# ESP32Schematic_1.net
KiCad netlist of a schematic drawn in Altium Designer
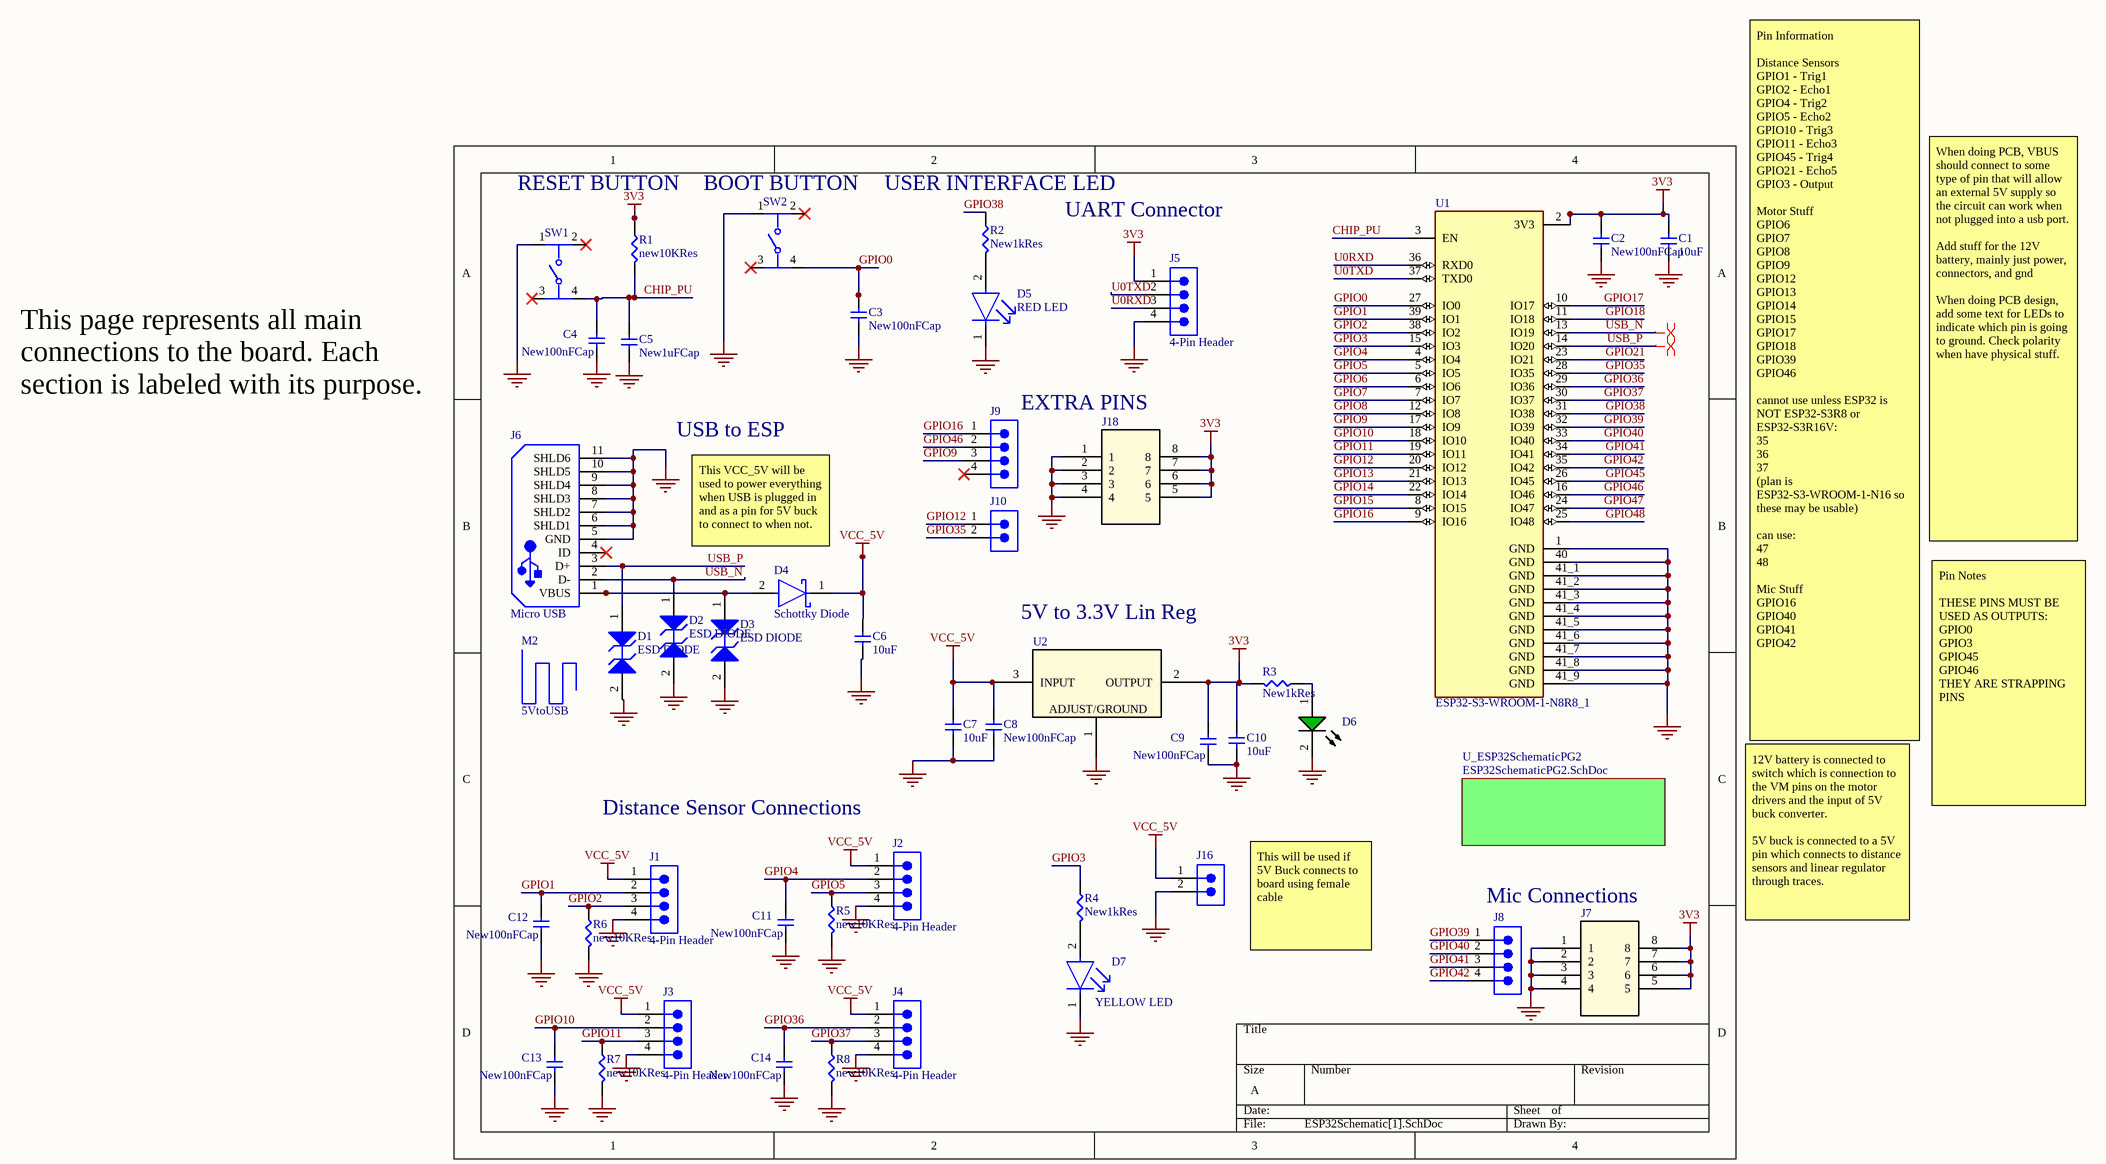
[diagram p0: ESP32Schematic[1].SchDoc]

(export (version "E")
  (design (tool "Eeschema 10.0.6"))
  (components
    (comp (ref "C1")
      (value "10uF")
      (footprint "FP-C0805C106K3PACTU-IPC_C")
      (description "0805 C 10UF Ceramic Multilayer Capacitor, 25 VDC, +85DEGC, X5R Dielec, +/-10%")
      (fields
        (field (name "MANUFACTURER") "KEMET")
        (field (name "MANUFACTURER PART NUMBER") "C0805C106K3PACTU")
      )
      (libsource (lib "Schlib") (part "C0805C106K3PACTU"))
    )
    (comp (ref "C2")
      (value "New100nFCap")
      (footprint "FP-CC0805-0_85-MFG")
      (description "25V 100nF X7R ±10% 0805 Multilayer Ceramic Capacitors MLCC - SMD/SMT ROHS")
      (fields
        (field (name "MANUFACTURER") "KEMET")
        (field (name "MANUFACTURER PART NUMBER") "C0805C104K3RACTU")
      )
      (libsource (lib "Schlib") (part "C0805C104K3RACTU"))
    )
    (comp (ref "C3")
      (value "New100nFCap")
      (footprint "FP-CC0805-0_85-MFG")
      (description "25V 100nF X7R ±10% 0805 Multilayer Ceramic Capacitors MLCC - SMD/SMT ROHS")
      (fields
        (field (name "MANUFACTURER") "KEMET")
        (field (name "MANUFACTURER PART NUMBER") "C0805C104K3RACTU")
      )
      (libsource (lib "Schlib") (part "C0805C104K3RACTU"))
    )
    (comp (ref "C4")
      (value "New100nFCap")
      (footprint "FP-CC0805-0_85-MFG")
      (description "25V 100nF X7R ±10% 0805 Multilayer Ceramic Capacitors MLCC - SMD/SMT ROHS")
      (fields
        (field (name "MANUFACTURER") "KEMET")
        (field (name "MANUFACTURER PART NUMBER") "C0805C104K3RACTU")
      )
      (libsource (lib "Schlib") (part "C0805C104K3RACTU"))
    )
    (comp (ref "C5")
      (value "New1uFCap")
      (footprint "CAPC2013X140X50ML20T25")
      (description "Multilayer Ceramic Capacitors MLCC – SMD/SMT; KEMET; C0805C105K3RACTU; 1 µF; 0805; 25 V; 25 V")
      (fields
        (field (name "MANUFACTURER") "KEMET")
        (field (name "MANUFACTURER PART NUMBER") "C0805C105K3RACTU")
      )
      (libsource (lib "Schlib") (part "C0805C105K3RACTU"))
    )
    (comp (ref "C6")
      (value "10uF")
      (footprint "FP-C0805C106K3PACTU-IPC_C")
      (description "0805 C 10UF Ceramic Multilayer Capacitor, 25 VDC, +85DEGC, X5R Dielec, +/-10%")
      (fields
        (field (name "MANUFACTURER") "KEMET")
        (field (name "MANUFACTURER PART NUMBER") "C0805C106K3PACTU")
      )
      (libsource (lib "Schlib") (part "C0805C106K3PACTU"))
    )
    (comp (ref "C7")
      (value "10uF")
      (footprint "FP-C0805C106K3PACTU-IPC_C")
      (description "0805 C 10UF Ceramic Multilayer Capacitor, 25 VDC, +85DEGC, X5R Dielec, +/-10%")
      (fields
        (field (name "MANUFACTURER") "KEMET")
        (field (name "MANUFACTURER PART NUMBER") "C0805C106K3PACTU")
      )
      (libsource (lib "Schlib") (part "C0805C106K3PACTU"))
    )
    (comp (ref "C8")
      (value "New100nFCap")
      (footprint "FP-CC0805-0_85-MFG")
      (description "25V 100nF X7R ±10% 0805 Multilayer Ceramic Capacitors MLCC - SMD/SMT ROHS")
      (fields
        (field (name "MANUFACTURER") "KEMET")
        (field (name "MANUFACTURER PART NUMBER") "C0805C104K3RACTU")
      )
      (libsource (lib "Schlib") (part "C0805C104K3RACTU"))
    )
    (comp (ref "C9")
      (value "New100nFCap")
      (footprint "FP-CC0805-0_85-MFG")
      (description "25V 100nF X7R ±10% 0805 Multilayer Ceramic Capacitors MLCC - SMD/SMT ROHS")
      (fields
        (field (name "MANUFACTURER") "KEMET")
        (field (name "MANUFACTURER PART NUMBER") "C0805C104K3RACTU")
      )
      (libsource (lib "Schlib") (part "C0805C104K3RACTU"))
    )
    (comp (ref "C10")
      (value "10uF")
      (footprint "FP-C0805C106K3PACTU-IPC_C")
      (description "0805 C 10UF Ceramic Multilayer Capacitor, 25 VDC, +85DEGC, X5R Dielec, +/-10%")
      (fields
        (field (name "MANUFACTURER") "KEMET")
        (field (name "MANUFACTURER PART NUMBER") "C0805C106K3PACTU")
      )
      (libsource (lib "Schlib") (part "C0805C106K3PACTU"))
    )
    (comp (ref "C11")
      (value "New100nFCap")
      (footprint "FP-CC0805-0_85-MFG")
      (description "25V 100nF X7R ±10% 0805 Multilayer Ceramic Capacitors MLCC - SMD/SMT ROHS")
      (fields
        (field (name "MANUFACTURER") "KEMET")
        (field (name "MANUFACTURER PART NUMBER") "C0805C104K3RACTU")
      )
      (libsource (lib "Schlib") (part "C0805C104K3RACTU"))
    )
    (comp (ref "C12")
      (value "New100nFCap")
      (footprint "FP-CC0805-0_85-MFG")
      (description "25V 100nF X7R ±10% 0805 Multilayer Ceramic Capacitors MLCC - SMD/SMT ROHS")
      (fields
        (field (name "MANUFACTURER") "KEMET")
        (field (name "MANUFACTURER PART NUMBER") "C0805C104K3RACTU")
      )
      (libsource (lib "Schlib") (part "C0805C104K3RACTU"))
    )
    (comp (ref "C13")
      (value "New100nFCap")
      (footprint "FP-CC0805-0_85-MFG")
      (description "25V 100nF X7R ±10% 0805 Multilayer Ceramic Capacitors MLCC - SMD/SMT ROHS")
      (fields
        (field (name "MANUFACTURER") "KEMET")
        (field (name "MANUFACTURER PART NUMBER") "C0805C104K3RACTU")
      )
      (libsource (lib "Schlib") (part "C0805C104K3RACTU"))
    )
    (comp (ref "C14")
      (value "New100nFCap")
      (footprint "FP-CC0805-0_85-MFG")
      (description "25V 100nF X7R ±10% 0805 Multilayer Ceramic Capacitors MLCC - SMD/SMT ROHS")
      (fields
        (field (name "MANUFACTURER") "KEMET")
        (field (name "MANUFACTURER PART NUMBER") "C0805C104K3RACTU")
      )
      (libsource (lib "Schlib") (part "C0805C104K3RACTU"))
    )
    (comp (ref "D1")
      (value "ESD DIODE")
      (footprint "ONSC-SOD-923-2-514AB-01_V")
      (description "5.8V Bidirectional 5V SOD-923 ESD and Surge Protection (TVS/ESD) ROHS")
      (fields (field (name "MANUFACTURER") "onsemi") (field (name "MANUFACTURER PART NUMBER") "ESD9B5.0ST5G"))
      (libsource (lib "Schlib") (part "ESD9B5.0ST5G"))
    )
    (comp (ref "D2")
      (value "ESD DIODE")
      (footprint "ONSC-SOD-923-2-514AB-01_V")
      (description "5.8V Bidirectional 5V SOD-923 ESD and Surge Protection (TVS/ESD) ROHS")
      (fields (field (name "MANUFACTURER") "onsemi") (field (name "MANUFACTURER PART NUMBER") "ESD9B5.0ST5G"))
      (libsource (lib "Schlib") (part "ESD9B5.0ST5G"))
    )
    (comp (ref "D3")
      (value "ESD DIODE")
      (footprint "ONSC-SOD-923-2-514AB-01_V")
      (description "5.8V Bidirectional 5V SOD-923 ESD and Surge Protection (TVS/ESD) ROHS")
      (fields (field (name "MANUFACTURER") "onsemi") (field (name "MANUFACTURER PART NUMBER") "ESD9B5.0ST5G"))
      (libsource (lib "Schlib") (part "ESD9B5.0ST5G"))
    )
    (comp (ref "D4")
      (value "Schottky Diode")
      (footprint "FP-SOD123-IPC_B")
      (description "1N5819HW Series 40 V 1 A Surface Mount Schottky Barrier Rectifier - SOD-123")
      (fields
        (field (name "MANUFACTURER") "Diodes Inc.")
        (field (name "MANUFACTURER PART NUMBER") "1N5819HW-7-F")
      )
      (libsource (lib "Schlib") (part "1N5819HW-7-F"))
    )
    (comp (ref "D5")
      (value "RED LED")
      (footprint "FP-HSMS-C150-MFG")
      (description "LED Uni-Color Hi-Eff. Red 630nm 2-Pin Chip LED T/R / LED RED DIFFUSED 1206 SMD")
      (fields (field (name "MANUFACTURER") "Avago") (field (name "MANUFACTURER PART NUMBER") "HSMS-C150"))
      (libsource (lib "Schlib") (part "HSMS-C150"))
    )
    (comp (ref "D6")
      (value "GREEN LED")
      (footprint "AVAG-HSMX-C110_V")
      (description "Surface Mount ChipLED Single Color LED, Green, Clear Untinted Nondiffused")
      (fields (field (name "MANUFACTURER") "Avago") (field (name "MANUFACTURER PART NUMBER") "HSMG-C110"))
      (libsource (lib "Schlib") (part "HSMG-C110"))
    )
    (comp (ref "D7")
      (value "YELLOW LED")
      (footprint "LED_HSMY-C170")
      (description "LED YELLOW DIFFUSED CHIP SMD Yellow 586nm LED Indication - Discrete 2.1V 0805 (2012 Metric)")
      (fields (field (name "MANUFACTURER") "Avago") (field (name "MANUFACTURER PART NUMBER") "HSMY-C170"))
      (libsource (lib "Schlib") (part "HSMY-C170"))
    )
    (comp (ref "J1")
      (value "4-Pin Header")
      (footprint "61300411121")
      (description "Conn Unshrouded Header HDR 4 POS 2.54mm Solder ST Thru-Hole Bag")
      (fields
        (field (name "MANUFACTURER") "Wurth Elektronik")
        (field (name "MANUFACTURER PART NUMBER") "61300411121")
      )
      (libsource (lib "Schlib") (part "61300411121"))
    )
    (comp (ref "J2")
      (value "4-Pin Header")
      (footprint "61300411121")
      (description "Conn Unshrouded Header HDR 4 POS 2.54mm Solder ST Thru-Hole Bag")
      (fields
        (field (name "MANUFACTURER") "Wurth Elektronik")
        (field (name "MANUFACTURER PART NUMBER") "61300411121")
      )
      (libsource (lib "Schlib") (part "61300411121"))
    )
    (comp (ref "J3")
      (value "4-Pin Header")
      (footprint "61300411121")
      (description "Conn Unshrouded Header HDR 4 POS 2.54mm Solder ST Thru-Hole Bag")
      (fields
        (field (name "MANUFACTURER") "Wurth Elektronik")
        (field (name "MANUFACTURER PART NUMBER") "61300411121")
      )
      (libsource (lib "Schlib") (part "61300411121"))
    )
    (comp (ref "J4")
      (value "4-Pin Header")
      (footprint "61300411121")
      (description "Conn Unshrouded Header HDR 4 POS 2.54mm Solder ST Thru-Hole Bag")
      (fields
        (field (name "MANUFACTURER") "Wurth Elektronik")
        (field (name "MANUFACTURER PART NUMBER") "61300411121")
      )
      (libsource (lib "Schlib") (part "61300411121"))
    )
    (comp (ref "J5")
      (value "4-Pin Header")
      (footprint "61300411121")
      (description "Conn Unshrouded Header HDR 4 POS 2.54mm Solder ST Thru-Hole Bag")
      (fields
        (field (name "MANUFACTURER") "Wurth Elektronik")
        (field (name "MANUFACTURER PART NUMBER") "61300411121")
      )
      (libsource (lib "Schlib") (part "61300411121"))
    )
    (comp (ref "J6")
      (value "Micro USB")
      (footprint "FCI-10103594-0001LF_V")
      (description "Usb Connector, 5 Contact(S), Female, Right Angle, Surface Mount Terminal, Locking, Receptacle")
      (fields
        (field (name "MANUFACTURER") "Amphenol Communications Solutions")
        (field (name "MANUFACTURER PART NUMBER") "10103594-0001LF")
      )
      (libsource (lib "Schlib") (part "10103594-0001LF"))
    )
    (comp (ref "J7")
      (value "8pin")
      (footprint "TSW-104-07-G-D_SAI")
      (description "Pin Header, Board-to-Board, 2.54 mm, 2 Rows, 8 Contacts, Through Hole, TSW Series")
      (fields
        (field (name "MANUFACTURER") "Samtec")
        (field (name "MANUFACTURER PART NUMBER") "TSW-104-07-F-D")
      )
      (libsource (lib "Schlib") (part "TSW-104-07-F-D"))
    )
    (comp (ref "J8")
      (value "4-Pin Header")
      (footprint "61300411121")
      (description "Conn Unshrouded Header HDR 4 POS 2.54mm Solder ST Thru-Hole Bag")
      (fields
        (field (name "MANUFACTURER") "Wurth Elektronik")
        (field (name "MANUFACTURER PART NUMBER") "61300411121")
      )
      (libsource (lib "Schlib") (part "61300411121"))
    )
    (comp (ref "J9")
      (value "4-Pin Header")
      (footprint "61300411121")
      (description "Conn Unshrouded Header HDR 4 POS 2.54mm Solder ST Thru-Hole Bag")
      (fields
        (field (name "MANUFACTURER") "Wurth Elektronik")
        (field (name "MANUFACTURER PART NUMBER") "61300411121")
      )
      (libsource (lib "Schlib") (part "61300411121"))
    )
    (comp (ref "J10")
      (value "2pinheader")
      (footprint "61300211121")
      (description "WR-PHD Straight Male, PCB Header, Through Hole, 1 Rows, 2 Contacts, 2.54mm Pitch")
      (fields
        (field (name "MANUFACTURER") "Wurth Elektronik")
        (field (name "MANUFACTURER PART NUMBER") "61300211121")
      )
      (libsource (lib "Schlib") (part "61300211121"))
    )
    (comp (ref "J16")
      (value "2pinheader")
      (footprint "61300211121")
      (description "WR-PHD Straight Male, PCB Header, Through Hole, 1 Rows, 2 Contacts, 2.54mm Pitch")
      (fields
        (field (name "MANUFACTURER") "Wurth Elektronik")
        (field (name "MANUFACTURER PART NUMBER") "61300211121")
      )
      (libsource (lib "Schlib") (part "61300211121"))
    )
    (comp (ref "J18")
      (value "8pin")
      (footprint "TSW-104-07-G-D_SAI")
      (description "Pin Header, Board-to-Board, 2.54 mm, 2 Rows, 8 Contacts, Through Hole, TSW Series")
      (fields
        (field (name "MANUFACTURER") "Samtec")
        (field (name "MANUFACTURER PART NUMBER") "TSW-104-07-F-D")
      )
      (libsource (lib "Schlib") (part "TSW-104-07-F-D"))
    )
    (comp (ref "M2")
      (value "5VtoUSB")
      (description "Usb Am to Usb Micro, Usb 2.0 - 1")
      (fields (field (name "MANUFACTURER") "CviLux") (field (name "MANUFACTURER PART NUMBER") "DH-20M50055"))
      (libsource (lib "Schlib") (part "DH-20M50055"))
    )
    (comp (ref "R1")
      (value "new10KRes")
      (footprint "RESC2013X60X35NL10T20")
      (description "Res Thick Film 0805 10K Ohm 1% 0.125W(1/8W) +/-100ppm/C Epoxy Pad SMD T/R")
      (fields
        (field (name "MANUFACTURER") "Yageo Group")
        (field (name "MANUFACTURER PART NUMBER") "RC0805FR-0710KL")
      )
      (libsource (lib "Schlib") (part "RC0805FR-0710KL"))
    )
    (comp (ref "R2")
      (value "New1kRes")
      (footprint "RESC2013X60X35NL10T20")
      (description "Yageo RC0805FR-071KL SMD Resistor 0603 1k Ohm ±1% Thick Film")
      (fields
        (field (name "MANUFACTURER") "Yageo Group")
        (field (name "MANUFACTURER PART NUMBER") "RC0805FR-071KL")
      )
      (libsource (lib "Schlib") (part "RC0805FR-071KL"))
    )
    (comp (ref "R3")
      (value "New1kRes")
      (footprint "RESC2013X60X35NL10T20")
      (description "Yageo RC0805FR-071KL SMD Resistor 0603 1k Ohm ±1% Thick Film")
      (fields
        (field (name "MANUFACTURER") "Yageo Group")
        (field (name "MANUFACTURER PART NUMBER") "RC0805FR-071KL")
      )
      (libsource (lib "Schlib") (part "RC0805FR-071KL"))
    )
    (comp (ref "R4")
      (value "New1kRes")
      (footprint "RESC2013X60X35NL10T20")
      (description "Yageo RC0805FR-071KL SMD Resistor 0603 1k Ohm ±1% Thick Film")
      (fields
        (field (name "MANUFACTURER") "Yageo Group")
        (field (name "MANUFACTURER PART NUMBER") "RC0805FR-071KL")
      )
      (libsource (lib "Schlib") (part "RC0805FR-071KL"))
    )
    (comp (ref "R5")
      (value "new10KRes")
      (footprint "RESC2013X60X35NL10T20")
      (description "Res Thick Film 0805 10K Ohm 1% 0.125W(1/8W) +/-100ppm/C Epoxy Pad SMD T/R")
      (fields
        (field (name "MANUFACTURER") "Yageo Group")
        (field (name "MANUFACTURER PART NUMBER") "RC0805FR-0710KL")
      )
      (libsource (lib "Schlib") (part "RC0805FR-0710KL"))
    )
    (comp (ref "R6")
      (value "new10KRes")
      (footprint "RESC2013X60X35NL10T20")
      (description "Res Thick Film 0805 10K Ohm 1% 0.125W(1/8W) +/-100ppm/C Epoxy Pad SMD T/R")
      (fields
        (field (name "MANUFACTURER") "Yageo Group")
        (field (name "MANUFACTURER PART NUMBER") "RC0805FR-0710KL")
      )
      (libsource (lib "Schlib") (part "RC0805FR-0710KL"))
    )
    (comp (ref "R7")
      (value "new10KRes")
      (footprint "RESC2013X60X35NL10T20")
      (description "Res Thick Film 0805 10K Ohm 1% 0.125W(1/8W) +/-100ppm/C Epoxy Pad SMD T/R")
      (fields
        (field (name "MANUFACTURER") "Yageo Group")
        (field (name "MANUFACTURER PART NUMBER") "RC0805FR-0710KL")
      )
      (libsource (lib "Schlib") (part "RC0805FR-0710KL"))
    )
    (comp (ref "R8")
      (value "new10KRes")
      (footprint "RESC2013X60X35NL10T20")
      (description "Res Thick Film 0805 10K Ohm 1% 0.125W(1/8W) +/-100ppm/C Epoxy Pad SMD T/R")
      (fields
        (field (name "MANUFACTURER") "Yageo Group")
        (field (name "MANUFACTURER PART NUMBER") "RC0805FR-0710KL")
      )
      (libsource (lib "Schlib") (part "RC0805FR-0710KL"))
    )
    (comp (ref "SW1")
      (value "PTS647SM38SMTR2LFS")
      (footprint "FP-PTS647SM38SMTR2LFS-MFG")
      (description "Switch Tactile OFF Mom SPST Round Button Gull Wing 50mA 12VDC 100000Cycles 1.77N Surface Mount T/R")
      (fields (field (name "MANUFACTURER") "C&K Components"))
      (libsource (lib "Schlib") (part "PTS647SM38SMTR2LFS"))
    )
    (comp (ref "SW2")
      (value "PTS647SM38SMTR2LFS")
      (footprint "FP-PTS647SM38SMTR2LFS-MFG")
      (description "Switch Tactile OFF Mom SPST Round Button Gull Wing 50mA 12VDC 100000Cycles 1.77N Surface Mount T/R")
      (fields (field (name "MANUFACTURER") "C&K Components"))
      (libsource (lib "Schlib") (part "PTS647SM38SMTR2LFS"))
    )
    (comp (ref "U1")
      (value "ESP32-S3-WROOM-1-N8R8_1")
      (footprint "XCVR_ESP32S3WROOM1N8R8")
      (description "SMD module, ESP32-S3R8 with 8 MB Octal PSRAM die inside, 8 MB Quad SPI flash, P")
      (fields (field (name "MF") "Espressif Systems") (field (name "MP") "ESP32-S3-WROOM-1-N8R8"))
      (libsource (lib "Schlib") (part "ESP32-S3-WROOM-1-N8R8_1"))
    )
    (comp (ref "U2")
      (value "LM1117MPX-33NOPB")
      (footprint "SOT223-318H_OSI")
      (description "800-mA 15-V linear voltage regulator 800-mA 15-V linear voltage regulator")
      (fields (field (name "MANUFACTURER") "onsemi"))
      (libsource (lib "Schlib") (part "LM1117MPX-33NOPB"))
    )
  )
  (nets
    (net (code "1") (name "/CHIP_PU") (class "Default")
      (node (ref "C4") (pin "2") (pinfunction "2_2") (pintype "passive"))
      (node (ref "C5") (pin "1") (pinfunction "1_1") (pintype "passive"))
      (node (ref "R1") (pin "2") (pinfunction "2_2") (pintype "passive"))
      (node (ref "SW1") (pin "4") (pinfunction "4_4") (pintype "passive"))
      (node (ref "U1") (pin "3") (pinfunction "EN_3") (pintype "passive"))
    )
    (net (code "2") (name "/GPIO0") (class "Default")
      (node (ref "C3") (pin "2") (pinfunction "2_2") (pintype "passive"))
      (node (ref "SW2") (pin "4") (pinfunction "4_4") (pintype "passive"))
      (node (ref "U1") (pin "27") (pinfunction "IO0_27") (pintype "bidirectional"))
    )
    (net (code "3") (name "/GPIO1") (class "Default")
      (node (ref "C12") (pin "2") (pinfunction "2_2") (pintype "passive"))
      (node (ref "J1") (pin "2") (pinfunction "2_2") (pintype "passive"))
      (node (ref "U1") (pin "39") (pinfunction "IO1_39") (pintype "bidirectional"))
    )
    (net (code "4") (name "/GPIO2") (class "Default")
      (node (ref "J1") (pin "3") (pinfunction "3_3") (pintype "passive"))
      (node (ref "R6") (pin "1") (pinfunction "1_1") (pintype "passive"))
      (node (ref "U1") (pin "38") (pinfunction "IO2_38") (pintype "bidirectional"))
    )
    (net (code "5") (name "/GPIO3") (class "Default")
      (node (ref "R4") (pin "1") (pinfunction "1_1") (pintype "passive"))
      (node (ref "U1") (pin "15") (pinfunction "IO3_15") (pintype "bidirectional"))
    )
    (net (code "6") (name "/GPIO4") (class "Default")
      (node (ref "C11") (pin "2") (pinfunction "2_2") (pintype "passive"))
      (node (ref "J2") (pin "2") (pinfunction "2_2") (pintype "passive"))
      (node (ref "U1") (pin "4") (pinfunction "IO4_4") (pintype "bidirectional"))
    )
    (net (code "7") (name "/GPIO5") (class "Default")
      (node (ref "J2") (pin "3") (pinfunction "3_3") (pintype "passive"))
      (node (ref "R5") (pin "1") (pinfunction "1_1") (pintype "passive"))
      (node (ref "U1") (pin "5") (pinfunction "IO5_5") (pintype "bidirectional"))
    )
    (net (code "8") (name "/GPIO6") (class "Default")
      (node (ref "U1") (pin "6") (pinfunction "IO6_6") (pintype "bidirectional"))
    )
    (net (code "9") (name "/GPIO7") (class "Default")
      (node (ref "U1") (pin "7") (pinfunction "IO7_7") (pintype "bidirectional"))
    )
    (net (code "10") (name "/GPIO8") (class "Default")
      (node (ref "U1") (pin "12") (pinfunction "IO8_12") (pintype "bidirectional"))
    )
    (net (code "11") (name "/GPIO9") (class "Default")
      (node (ref "J9") (pin "3") (pinfunction "3_3") (pintype "passive"))
      (node (ref "U1") (pin "17") (pinfunction "IO9_17") (pintype "bidirectional"))
    )
    (net (code "12") (name "/GPIO10") (class "Default")
      (node (ref "C13") (pin "2") (pinfunction "2_2") (pintype "passive"))
      (node (ref "J3") (pin "2") (pinfunction "2_2") (pintype "passive"))
      (node (ref "U1") (pin "18") (pinfunction "IO10_18") (pintype "bidirectional"))
    )
    (net (code "13") (name "/GPIO11") (class "Default")
      (node (ref "J3") (pin "3") (pinfunction "3_3") (pintype "passive"))
      (node (ref "R7") (pin "1") (pinfunction "1_1") (pintype "passive"))
      (node (ref "U1") (pin "19") (pinfunction "IO11_19") (pintype "bidirectional"))
    )
    (net (code "14") (name "/GPIO12") (class "Default")
      (node (ref "J10") (pin "1") (pinfunction "1_1") (pintype "passive"))
      (node (ref "U1") (pin "20") (pinfunction "IO12_20") (pintype "bidirectional"))
    )
    (net (code "15") (name "/GPIO13") (class "Default")
      (node (ref "U1") (pin "21") (pinfunction "IO13_21") (pintype "bidirectional"))
    )
    (net (code "16") (name "/GPIO14") (class "Default")
      (node (ref "U1") (pin "22") (pinfunction "IO14_22") (pintype "bidirectional"))
    )
    (net (code "17") (name "/GPIO15") (class "Default")
      (node (ref "U1") (pin "8") (pinfunction "IO15_8") (pintype "bidirectional"))
    )
    (net (code "18") (name "/GPIO16") (class "Default")
      (node (ref "J9") (pin "1") (pinfunction "1_1") (pintype "passive"))
      (node (ref "U1") (pin "9") (pinfunction "IO16_9") (pintype "bidirectional"))
    )
    (net (code "19") (name "/GPIO17") (class "Default")
      (node (ref "U1") (pin "10") (pinfunction "IO17_10") (pintype "bidirectional"))
    )
    (net (code "20") (name "/GPIO18") (class "Default")
      (node (ref "U1") (pin "11") (pinfunction "IO18_11") (pintype "bidirectional"))
    )
    (net (code "21") (name "/GPIO21") (class "Default")
      (node (ref "U1") (pin "23") (pinfunction "IO21_23") (pintype "bidirectional"))
    )
    (net (code "22") (name "/GPIO35") (class "Default")
      (node (ref "J10") (pin "2") (pinfunction "2_2") (pintype "passive"))
      (node (ref "U1") (pin "28") (pinfunction "IO35_28") (pintype "bidirectional"))
    )
    (net (code "23") (name "/GPIO36") (class "Default")
      (node (ref "C14") (pin "2") (pinfunction "2_2") (pintype "passive"))
      (node (ref "J4") (pin "2") (pinfunction "2_2") (pintype "passive"))
      (node (ref "U1") (pin "29") (pinfunction "IO36_29") (pintype "bidirectional"))
    )
    (net (code "24") (name "/GPIO37") (class "Default")
      (node (ref "J4") (pin "3") (pinfunction "3_3") (pintype "passive"))
      (node (ref "R8") (pin "1") (pinfunction "1_1") (pintype "passive"))
      (node (ref "U1") (pin "30") (pinfunction "IO37_30") (pintype "bidirectional"))
    )
    (net (code "25") (name "/GPIO38") (class "Default")
      (node (ref "R2") (pin "1") (pinfunction "1_1") (pintype "passive"))
      (node (ref "U1") (pin "31") (pinfunction "IO38_31") (pintype "bidirectional"))
    )
    (net (code "26") (name "/GPIO39") (class "Default")
      (node (ref "J8") (pin "1") (pinfunction "1_1") (pintype "passive"))
      (node (ref "U1") (pin "32") (pinfunction "IO39_32") (pintype "bidirectional"))
    )
    (net (code "27") (name "/GPIO40") (class "Default")
      (node (ref "J8") (pin "2") (pinfunction "2_2") (pintype "passive"))
      (node (ref "U1") (pin "33") (pinfunction "IO40_33") (pintype "bidirectional"))
    )
    (net (code "28") (name "/GPIO41") (class "Default")
      (node (ref "J8") (pin "3") (pinfunction "3_3") (pintype "passive"))
      (node (ref "U1") (pin "34") (pinfunction "IO41_34") (pintype "bidirectional"))
    )
    (net (code "29") (name "/GPIO42") (class "Default")
      (node (ref "J8") (pin "4") (pinfunction "4_4") (pintype "passive"))
      (node (ref "U1") (pin "35") (pinfunction "IO42_35") (pintype "bidirectional"))
    )
    (net (code "30") (name "/GPIO45") (class "Default")
      (node (ref "U1") (pin "26") (pinfunction "IO45_26") (pintype "bidirectional"))
    )
    (net (code "31") (name "/GPIO46") (class "Default")
      (node (ref "J9") (pin "2") (pinfunction "2_2") (pintype "passive"))
      (node (ref "U1") (pin "16") (pinfunction "IO46_16") (pintype "bidirectional"))
    )
    (net (code "32") (name "/GPIO47") (class "Default")
      (node (ref "U1") (pin "24") (pinfunction "IO47_24") (pintype "bidirectional"))
    )
    (net (code "33") (name "/GPIO48") (class "Default")
      (node (ref "U1") (pin "25") (pinfunction "IO48_25") (pintype "bidirectional"))
    )
    (net (code "34") (name "/U0RXD") (class "Default")
      (node (ref "J5") (pin "3") (pinfunction "3_3") (pintype "passive"))
      (node (ref "U1") (pin "36") (pinfunction "RXD0_36") (pintype "bidirectional"))
    )
    (net (code "35") (name "/U0TXD") (class "Default")
      (node (ref "J5") (pin "2") (pinfunction "2_2") (pintype "passive"))
      (node (ref "U1") (pin "37") (pinfunction "TXD0_37") (pintype "bidirectional"))
    )
    (net (code "36") (name "/USB_N") (class "Default")
      (node (ref "D2") (pin "1") (pinfunction "A1_1") (pintype "passive"))
      (node (ref "J6") (pin "2") (pinfunction "D-_2") (pintype "passive"))
      (node (ref "U1") (pin "13") (pinfunction "IO19_13") (pintype "bidirectional"))
    )
    (net (code "37") (name "/USB_P") (class "Default")
      (node (ref "D1") (pin "1") (pinfunction "A1_1") (pintype "passive"))
      (node (ref "J6") (pin "3") (pinfunction "D+_3") (pintype "passive"))
      (node (ref "U1") (pin "14") (pinfunction "IO20_14") (pintype "bidirectional"))
    )
    (net (code "38") (name "3V3") (class "Default")
      (node (ref "C1") (pin "2") (pinfunction "2_2") (pintype "passive"))
      (node (ref "C10") (pin "2") (pinfunction "2_2") (pintype "passive"))
      (node (ref "C2") (pin "2") (pinfunction "2_2") (pintype "passive"))
      (node (ref "C9") (pin "2") (pinfunction "2_2") (pintype "passive"))
      (node (ref "J18") (pin "5") (pinfunction "5_5") (pintype "passive"))
      (node (ref "J18") (pin "6") (pinfunction "6_6") (pintype "passive"))
      (node (ref "J18") (pin "7") (pinfunction "7_7") (pintype "passive"))
      (node (ref "J18") (pin "8") (pinfunction "8_8") (pintype "passive"))
      (node (ref "J5") (pin "1") (pinfunction "1_1") (pintype "passive"))
      (node (ref "J7") (pin "5") (pinfunction "5_5") (pintype "passive"))
      (node (ref "J7") (pin "6") (pinfunction "6_6") (pintype "passive"))
      (node (ref "J7") (pin "7") (pinfunction "7_7") (pintype "passive"))
      (node (ref "J7") (pin "8") (pinfunction "8_8") (pintype "passive"))
      (node (ref "R1") (pin "1") (pinfunction "1_1") (pintype "passive"))
      (node (ref "R3") (pin "2") (pinfunction "2_2") (pintype "passive"))
      (node (ref "U1") (pin "2") (pinfunction "3V3_2") (pintype "power_in"))
      (node (ref "U2") (pin "2") (pinfunction "OUTPUT_2") (pintype "power_in"))
    )
    (net (code "39") (name "GND") (class "Default")
      (node (ref "C1") (pin "1") (pinfunction "1_1") (pintype "passive"))
      (node (ref "C10") (pin "1") (pinfunction "1_1") (pintype "passive"))
      (node (ref "C11") (pin "1") (pinfunction "1_1") (pintype "passive"))
      (node (ref "C12") (pin "1") (pinfunction "1_1") (pintype "passive"))
      (node (ref "C13") (pin "1") (pinfunction "1_1") (pintype "passive"))
      (node (ref "C14") (pin "1") (pinfunction "1_1") (pintype "passive"))
      (node (ref "C2") (pin "1") (pinfunction "1_1") (pintype "passive"))
      (node (ref "C3") (pin "1") (pinfunction "1_1") (pintype "passive"))
      (node (ref "C4") (pin "1") (pinfunction "1_1") (pintype "passive"))
      (node (ref "C5") (pin "2") (pinfunction "2_2") (pintype "passive"))
      (node (ref "C6") (pin "1") (pinfunction "1_1") (pintype "passive"))
      (node (ref "C7") (pin "1") (pinfunction "1_1") (pintype "passive"))
      (node (ref "C8") (pin "1") (pinfunction "1_1") (pintype "passive"))
      (node (ref "C9") (pin "1") (pinfunction "1_1") (pintype "passive"))
      (node (ref "D1") (pin "2") (pinfunction "A2_2") (pintype "passive"))
      (node (ref "D2") (pin "2") (pinfunction "A2_2") (pintype "passive"))
      (node (ref "D3") (pin "2") (pinfunction "A2_2") (pintype "passive"))
      (node (ref "D5") (pin "1") (pinfunction "C_1") (pintype "passive"))
      (node (ref "D6") (pin "2") (pinfunction "K_2") (pintype "passive"))
      (node (ref "D7") (pin "1") (pinfunction "C_1") (pintype "passive"))
      (node (ref "J1") (pin "4") (pinfunction "4_4") (pintype "passive"))
      (node (ref "J16") (pin "2") (pinfunction "2_2") (pintype "passive"))
      (node (ref "J18") (pin "1") (pinfunction "1_1") (pintype "passive"))
      (node (ref "J18") (pin "2") (pinfunction "2_2") (pintype "passive"))
      (node (ref "J18") (pin "3") (pinfunction "3_3") (pintype "passive"))
      (node (ref "J18") (pin "4") (pinfunction "4_4") (pintype "passive"))
      (node (ref "J2") (pin "4") (pinfunction "4_4") (pintype "passive"))
      (node (ref "J3") (pin "4") (pinfunction "4_4") (pintype "passive"))
      (node (ref "J4") (pin "4") (pinfunction "4_4") (pintype "passive"))
      (node (ref "J5") (pin "4") (pinfunction "4_4") (pintype "passive"))
      (node (ref "J6") (pin "10") (pinfunction "SHLD5_10") (pintype "passive"))
      (node (ref "J6") (pin "11") (pinfunction "SHLD6_11") (pintype "passive"))
      (node (ref "J6") (pin "5") (pinfunction "GND_5") (pintype "passive"))
      (node (ref "J6") (pin "6") (pinfunction "SHLD1_6") (pintype "passive"))
      (node (ref "J6") (pin "7") (pinfunction "SHLD2_7") (pintype "passive"))
      (node (ref "J6") (pin "8") (pinfunction "SHLD3_8") (pintype "passive"))
      (node (ref "J6") (pin "9") (pinfunction "SHLD4_9") (pintype "passive"))
      (node (ref "J7") (pin "1") (pinfunction "1_1") (pintype "passive"))
      (node (ref "J7") (pin "2") (pinfunction "2_2") (pintype "passive"))
      (node (ref "J7") (pin "3") (pinfunction "3_3") (pintype "passive"))
      (node (ref "J7") (pin "4") (pinfunction "4_4") (pintype "passive"))
      (node (ref "R5") (pin "2") (pinfunction "2_2") (pintype "passive"))
      (node (ref "R6") (pin "2") (pinfunction "2_2") (pintype "passive"))
      (node (ref "R7") (pin "2") (pinfunction "2_2") (pintype "passive"))
      (node (ref "R8") (pin "2") (pinfunction "2_2") (pintype "passive"))
      (node (ref "SW1") (pin "1") (pinfunction "1_1") (pintype "passive"))
      (node (ref "SW2") (pin "1") (pinfunction "1_1") (pintype "passive"))
      (node (ref "U1") (pin "1") (pinfunction "GND_1") (pintype "power_in"))
      (node (ref "U1") (pin "40") (pinfunction "GND_40") (pintype "power_in"))
      (node (ref "U1") (pin "41_1") (pinfunction "GND_41_1") (pintype "power_in"))
      (node (ref "U1") (pin "41_2") (pinfunction "GND_41_2") (pintype "power_in"))
      (node (ref "U1") (pin "41_3") (pinfunction "GND_41_3") (pintype "power_in"))
      (node (ref "U1") (pin "41_4") (pinfunction "GND_41_4") (pintype "power_in"))
      (node (ref "U1") (pin "41_5") (pinfunction "GND_41_5") (pintype "power_in"))
      (node (ref "U1") (pin "41_6") (pinfunction "GND_41_6") (pintype "power_in"))
      (node (ref "U1") (pin "41_7") (pinfunction "GND_41_7") (pintype "power_in"))
      (node (ref "U1") (pin "41_8") (pinfunction "GND_41_8") (pintype "power_in"))
      (node (ref "U1") (pin "41_9") (pinfunction "GND_41_9") (pintype "power_in"))
      (node (ref "U2") (pin "1") (pinfunction "ADJUST/GROUND_1") (pintype "passive"))
    )
    (net (code "40") (name "Net-(D3-A1)") (class "Default")
      (node (ref "D3") (pin "1") (pinfunction "A1_1") (pintype "passive"))
      (node (ref "D4") (pin "2") (pinfunction "A_2") (pintype "passive"))
      (node (ref "J6") (pin "1") (pinfunction "VBUS_1") (pintype "passive"))
    )
    (net (code "41") (name "Net-(D5-A)") (class "Default")
      (node (ref "D5") (pin "2") (pinfunction "A_2") (pintype "passive"))
      (node (ref "R2") (pin "2") (pinfunction "2_2") (pintype "passive"))
    )
    (net (code "42") (name "Net-(D6-A)") (class "Default")
      (node (ref "D6") (pin "1") (pinfunction "A_1") (pintype "passive"))
      (node (ref "R3") (pin "1") (pinfunction "1_1") (pintype "passive"))
    )
    (net (code "43") (name "Net-(D7-A)") (class "Default")
      (node (ref "D7") (pin "2") (pinfunction "A_2") (pintype "passive"))
      (node (ref "R4") (pin "2") (pinfunction "2_2") (pintype "passive"))
    )
    (net (code "44") (name "VCC_5V") (class "Default")
      (node (ref "C6") (pin "2") (pinfunction "2_2") (pintype "passive"))
      (node (ref "C7") (pin "2") (pinfunction "2_2") (pintype "passive"))
      (node (ref "C8") (pin "2") (pinfunction "2_2") (pintype "passive"))
      (node (ref "D4") (pin "1") (pinfunction "C_1") (pintype "passive"))
      (node (ref "J1") (pin "1") (pinfunction "1_1") (pintype "passive"))
      (node (ref "J16") (pin "1") (pinfunction "1_1") (pintype "passive"))
      (node (ref "J2") (pin "1") (pinfunction "1_1") (pintype "passive"))
      (node (ref "J3") (pin "1") (pinfunction "1_1") (pintype "passive"))
      (node (ref "J4") (pin "1") (pinfunction "1_1") (pintype "passive"))
      (node (ref "U2") (pin "3") (pinfunction "INPUT_3") (pintype "passive"))
    )
    (net (code "45") (name "unconnected-(J6-ID-Pad4)") (class "Default")
      (node (ref "J6") (pin "4") (pinfunction "ID_4") (pintype "passive+no_connect"))
    )
    (net (code "46") (name "unconnected-(J9-Pad4)") (class "Default")
      (node (ref "J9") (pin "4") (pinfunction "4_4") (pintype "passive+no_connect"))
    )
    (net (code "47") (name "unconnected-(SW1-Pad2)") (class "Default")
      (node (ref "SW1") (pin "2") (pinfunction "2_2") (pintype "passive+no_connect"))
    )
    (net (code "48") (name "unconnected-(SW1-Pad3)") (class "Default")
      (node (ref "SW1") (pin "3") (pinfunction "3_3") (pintype "passive+no_connect"))
    )
    (net (code "49") (name "unconnected-(SW2-Pad2)") (class "Default")
      (node (ref "SW2") (pin "2") (pinfunction "2_2") (pintype "passive+no_connect"))
    )
    (net (code "50") (name "unconnected-(SW2-Pad3)") (class "Default")
      (node (ref "SW2") (pin "3") (pinfunction "3_3") (pintype "passive+no_connect"))
    )
  )
)
